# 04-ES8311-PA.net
KiCad netlist of a schematic drawn in EasyEDA
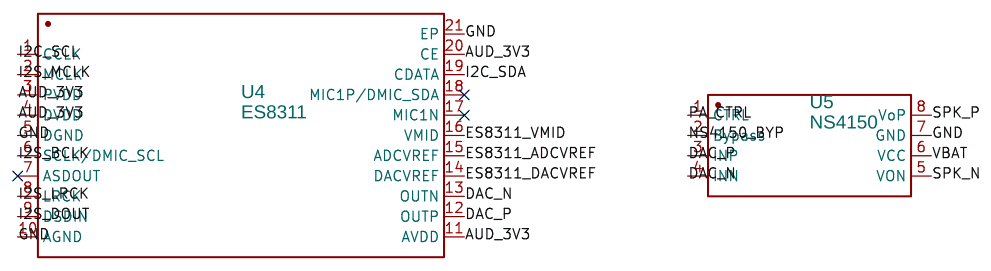
[diagram p0: schematic sheet]

(export (version "E")
  (design (tool "Eeschema 10.0.6"))
  (components
    (comp (ref "U4")
      (value "ES8311")
      (fields (field (name "Manufacturer") "Everest-semi()"))
      (libsource (lib "") (part "Unknown_400.0_300.0"))
    )
    (comp (ref "U5")
      (value "NS4150")
      (fields (field (name "Manufacturer Part") "NS4150B") (field (name "Manufacturer") "Nsiway()"))
      (libsource (lib "") (part "Unknown_680.0_305.0"))
    )
  )
  (nets
    (net (code "1") (name "/AUD_3V3") (class "Default")
      (node (ref "U4") (pin "11") (pinfunction "AVDD_11") (pintype "unspecified"))
      (node (ref "U4") (pin "20") (pinfunction "CE_20") (pintype "unspecified"))
      (node (ref "U4") (pin "3") (pinfunction "PVDD_3") (pintype "unspecified"))
      (node (ref "U4") (pin "4") (pinfunction "DVDD_4") (pintype "unspecified"))
    )
    (net (code "2") (name "/DAC_N") (class "Default")
      (node (ref "U4") (pin "13") (pinfunction "OUTN_13") (pintype "unspecified"))
      (node (ref "U5") (pin "4") (pinfunction "INN_4") (pintype "unspecified"))
    )
    (net (code "3") (name "/DAC_P") (class "Default")
      (node (ref "U4") (pin "12") (pinfunction "OUTP_12") (pintype "unspecified"))
      (node (ref "U5") (pin "3") (pinfunction "INP_3") (pintype "unspecified"))
    )
    (net (code "4") (name "/ES8311_ADCVREF") (class "Default")
      (node (ref "U4") (pin "15") (pinfunction "ADCVREF_15") (pintype "unspecified"))
    )
    (net (code "5") (name "/ES8311_DACVREF") (class "Default")
      (node (ref "U4") (pin "14") (pinfunction "DACVREF_14") (pintype "unspecified"))
    )
    (net (code "6") (name "/ES8311_VMID") (class "Default")
      (node (ref "U4") (pin "16") (pinfunction "VMID_16") (pintype "unspecified"))
    )
    (net (code "7") (name "/GND") (class "Default")
      (node (ref "U4") (pin "10") (pinfunction "AGND_10") (pintype "unspecified"))
      (node (ref "U4") (pin "21") (pinfunction "EP_21") (pintype "unspecified"))
      (node (ref "U4") (pin "5") (pinfunction "DGND_5") (pintype "unspecified"))
      (node (ref "U5") (pin "7") (pinfunction "GND_7") (pintype "unspecified"))
    )
    (net (code "8") (name "/I2C_SCL") (class "Default")
      (node (ref "U4") (pin "1") (pinfunction "CCLK_1") (pintype "unspecified"))
    )
    (net (code "9") (name "/I2C_SDA") (class "Default")
      (node (ref "U4") (pin "19") (pinfunction "CDATA_19") (pintype "unspecified"))
    )
    (net (code "10") (name "/I2S_BCLK") (class "Default")
      (node (ref "U4") (pin "6") (pinfunction "SCLK/DMIC_SCL_6") (pintype "unspecified"))
    )
    (net (code "11") (name "/I2S_DOUT") (class "Default")
      (node (ref "U4") (pin "9") (pinfunction "DSDIN_9") (pintype "unspecified"))
    )
    (net (code "12") (name "/I2S_LRCK") (class "Default")
      (node (ref "U4") (pin "8") (pinfunction "LRCK_8") (pintype "unspecified"))
    )
    (net (code "13") (name "/I2S_MCLK") (class "Default")
      (node (ref "U4") (pin "2") (pinfunction "MCLK_2") (pintype "unspecified"))
    )
    (net (code "14") (name "/NS4150_BYP") (class "Default")
      (node (ref "U5") (pin "2") (pinfunction "Bypass_2") (pintype "unspecified"))
    )
    (net (code "15") (name "/PA_CTRL") (class "Default")
      (node (ref "U5") (pin "1") (pinfunction "CTRL_1") (pintype "unspecified"))
    )
    (net (code "16") (name "/SPK_N") (class "Default")
      (node (ref "U5") (pin "5") (pinfunction "VON_5") (pintype "unspecified"))
    )
    (net (code "17") (name "/SPK_P") (class "Default")
      (node (ref "U5") (pin "8") (pinfunction "VoP_8") (pintype "unspecified"))
    )
    (net (code "18") (name "/VBAT") (class "Default")
      (node (ref "U5") (pin "6") (pinfunction "VCC_6") (pintype "unspecified"))
    )
    (net (code "19") (name "unconnected-(U4-ASDOUT-Pad7)") (class "Default")
      (node (ref "U4") (pin "7") (pinfunction "ASDOUT_7") (pintype "unspecified+no_connect"))
    )
    (net (code "20") (name "unconnected-(U4-MIC1N-Pad17)") (class "Default")
      (node (ref "U4") (pin "17") (pinfunction "MIC1N_17") (pintype "unspecified+no_connect"))
    )
    (net (code "21") (name "unconnected-(U4-MIC1P{slash}DMIC_SDA-Pad18)") (class "Default")
      (node (ref "U4") (pin "18") (pinfunction "MIC1P/DMIC_SDA_18") (pintype "unspecified+no_connect"))
    )
  )
)
